# trigger_pickoff.net
KiCad netlist of a schematic drawn in EAGLE
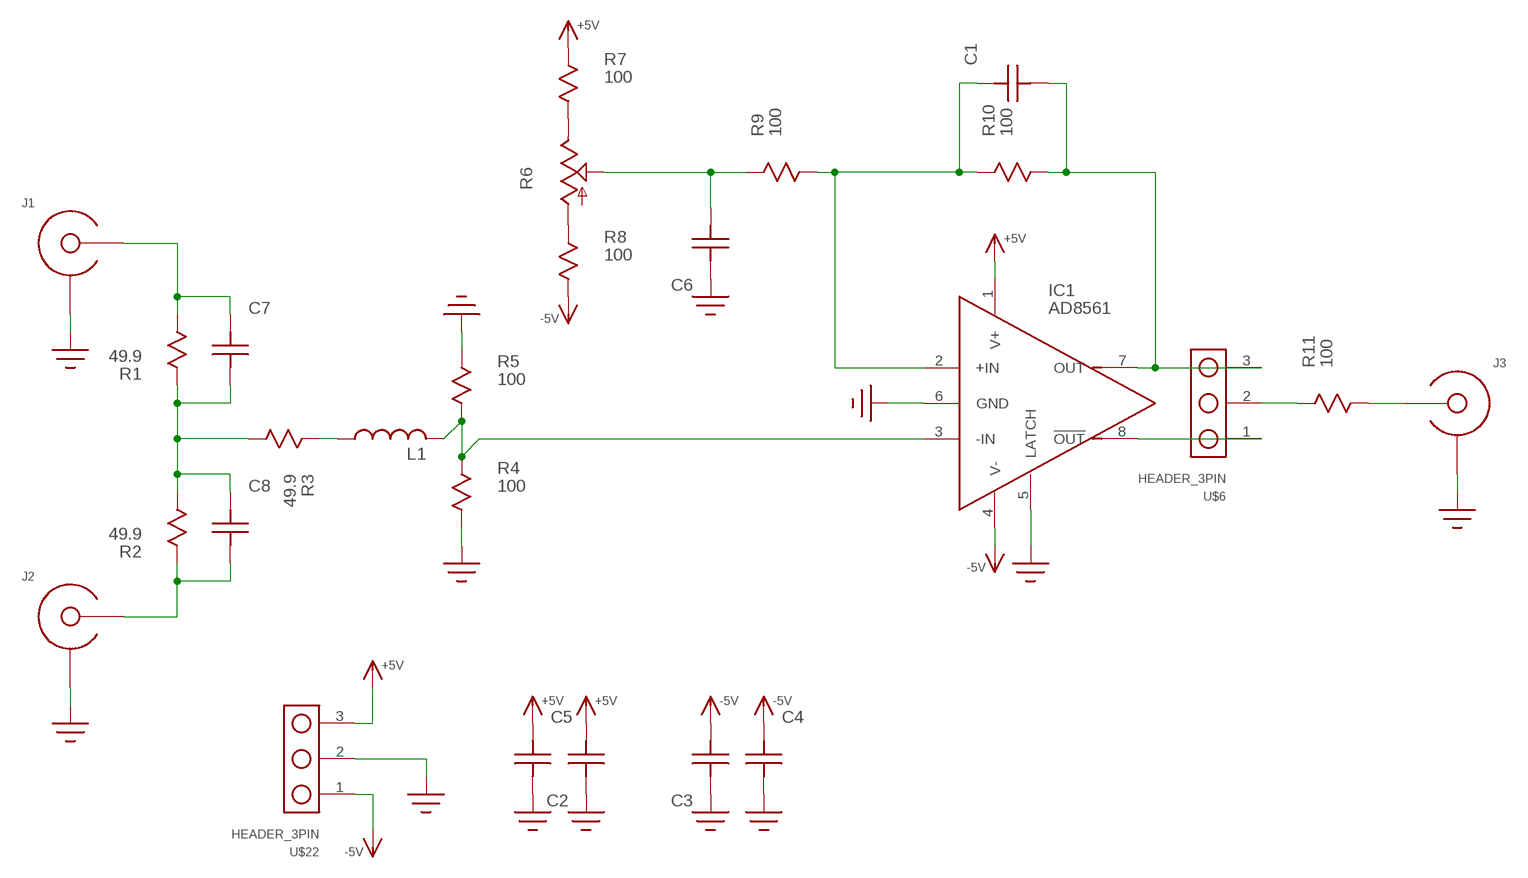
[diagram p0: schematic, sheet 1]

(export (version "E")
  (design (tool "Eeschema 10.0.6"))
  (components
    (comp (ref "C1")
      (value "C0603")
      (footprint "eagle-import:C0603")
      (libsource (lib "eagle-import") (part "C0603"))
    )
    (comp (ref "C2")
      (value "C0603")
      (footprint "eagle-import:C0603")
      (libsource (lib "eagle-import") (part "C0603"))
    )
    (comp (ref "C3")
      (value "C0603")
      (footprint "eagle-import:C0603")
      (libsource (lib "eagle-import") (part "C0603"))
    )
    (comp (ref "C4")
      (value "C0805")
      (footprint "eagle-import:0805")
      (libsource (lib "eagle-import") (part "C0805"))
    )
    (comp (ref "C5")
      (value "C0805")
      (footprint "eagle-import:0805")
      (libsource (lib "eagle-import") (part "C0805"))
    )
    (comp (ref "C6")
      (value "C0603")
      (footprint "eagle-import:C0603")
      (libsource (lib "eagle-import") (part "C0603"))
    )
    (comp (ref "C7")
      (value "C0603")
      (footprint "eagle-import:C0603")
      (libsource (lib "eagle-import") (part "C0603"))
    )
    (comp (ref "C8")
      (value "C0603")
      (footprint "eagle-import:C0603")
      (libsource (lib "eagle-import") (part "C0603"))
    )
    (comp (ref "IC1")
      (value "AD8561")
      (footprint "eagle-import:SOIC8")
      (libsource (lib "eagle-import") (part "AD8561"))
    )
    (comp (ref "J1")
      (value "EDGE_LAUNCH_JACK")
      (footprint "eagle-import:EDGE_LAUNCH_RF_CON")
      (libsource (lib "eagle-import") (part "EDGE_LAUNCH_JACK"))
    )
    (comp (ref "J2")
      (value "EDGE_LAUNCH_JACK")
      (footprint "eagle-import:EDGE_LAUNCH_RF_CON")
      (libsource (lib "eagle-import") (part "EDGE_LAUNCH_JACK"))
    )
    (comp (ref "J3")
      (value "EDGE_LAUNCH_JACK")
      (footprint "eagle-import:EDGE_LAUNCH_RF_CON")
      (libsource (lib "eagle-import") (part "EDGE_LAUNCH_JACK"))
    )
    (comp (ref "L1")
      (value "INDUCTOR")
      (footprint "eagle-import:R0603")
      (libsource (lib "eagle-import") (part "INDUCTOR"))
    )
    (comp (ref "R1")
      (value "49.9")
      (footprint "eagle-import:R0603")
      (libsource (lib "eagle-import") (part "R0603"))
    )
    (comp (ref "R2")
      (value "49.9")
      (footprint "eagle-import:R0603")
      (libsource (lib "eagle-import") (part "R0603"))
    )
    (comp (ref "R3")
      (value "49.9")
      (footprint "eagle-import:R0603")
      (libsource (lib "eagle-import") (part "R0603"))
    )
    (comp (ref "R4")
      (value "100")
      (footprint "eagle-import:R0603")
      (libsource (lib "eagle-import") (part "R0603"))
    )
    (comp (ref "R5")
      (value "100")
      (footprint "eagle-import:R0603")
      (libsource (lib "eagle-import") (part "R0603"))
    )
    (comp (ref "R6")
      (value "TRIM_US-SP19L")
      (footprint "eagle-import:SP19L")
      (libsource (lib "eagle-import") (part "TRIM_US-SP19L"))
    )
    (comp (ref "R7")
      (value "100")
      (footprint "eagle-import:R0603")
      (libsource (lib "eagle-import") (part "R0603"))
    )
    (comp (ref "R8")
      (value "100")
      (footprint "eagle-import:R0603")
      (libsource (lib "eagle-import") (part "R0603"))
    )
    (comp (ref "R9")
      (value "100")
      (footprint "eagle-import:R0603")
      (libsource (lib "eagle-import") (part "R0603"))
    )
    (comp (ref "R10")
      (value "100")
      (footprint "eagle-import:R0603")
      (libsource (lib "eagle-import") (part "R0603"))
    )
    (comp (ref "R11")
      (value "100")
      (footprint "eagle-import:R0603")
      (libsource (lib "eagle-import") (part "R0603"))
    )
    (comp (ref "U$6")
      (value "HEADER_3PIN")
      (footprint "eagle-import:HEADER_3PIN")
      (libsource (lib "eagle-import") (part "HEADER_3PIN"))
    )
    (comp (ref "U$22")
      (value "HEADER_3PIN")
      (footprint "eagle-import:HEADER_3PIN")
      (libsource (lib "eagle-import") (part "HEADER_3PIN"))
    )
  )
  (nets
    (net (code "1") (name "+5V") (class "Default")
      (node (ref "C2") (pin "P$1") (pinfunction "P$1_P$1") (pintype "bidirectional"))
      (node (ref "C5") (pin "P$2") (pinfunction "P$2_P$2") (pintype "bidirectional"))
      (node (ref "IC1") (pin "1") (pinfunction "V+_1") (pintype "bidirectional"))
      (node (ref "R7") (pin "P$1") (pinfunction "P$3_P$1") (pintype "bidirectional"))
      (node (ref "U$22") (pin "3") (pinfunction "3_3") (pintype "bidirectional"))
    )
    (net (code "2") (name "-5V") (class "Default")
      (node (ref "C3") (pin "P$1") (pinfunction "P$1_P$1") (pintype "bidirectional"))
      (node (ref "C4") (pin "P$2") (pinfunction "P$2_P$2") (pintype "bidirectional"))
      (node (ref "IC1") (pin "4") (pinfunction "V-_4") (pintype "bidirectional"))
      (node (ref "R8") (pin "P$2") (pinfunction "P$4_P$2") (pintype "bidirectional"))
      (node (ref "U$22") (pin "1") (pinfunction "1_1") (pintype "bidirectional"))
    )
    (net (code "3") (name "GND") (class "Default")
      (node (ref "C2") (pin "P$2") (pinfunction "P$2_P$2") (pintype "bidirectional"))
      (node (ref "C3") (pin "P$2") (pinfunction "P$2_P$2") (pintype "bidirectional"))
      (node (ref "C4") (pin "P$1") (pinfunction "P$1_P$1") (pintype "bidirectional"))
      (node (ref "C5") (pin "P$1") (pinfunction "P$1_P$1") (pintype "bidirectional"))
      (node (ref "C6") (pin "P$2") (pinfunction "P$2_P$2") (pintype "bidirectional"))
      (node (ref "IC1") (pin "5") (pinfunction "LATCH_5") (pintype "bidirectional"))
      (node (ref "IC1") (pin "6") (pinfunction "GND_6") (pintype "bidirectional"))
      (node (ref "J1") (pin "GND@1") (pinfunction "SHIELD_GND@1") (pintype "bidirectional"))
      (node (ref "J1") (pin "GND@10") (pinfunction "SHIELD_GND@10") (pintype "bidirectional"))
      (node (ref "J1") (pin "GND@11") (pinfunction "SHIELD_GND@11") (pintype "bidirectional"))
      (node (ref "J1") (pin "GND@12") (pinfunction "SHIELD_GND@12") (pintype "bidirectional"))
      (node (ref "J1") (pin "GND@2") (pinfunction "SHIELD_GND@2") (pintype "bidirectional"))
      (node (ref "J1") (pin "GND@3") (pinfunction "SHIELD_GND@3") (pintype "bidirectional"))
      (node (ref "J1") (pin "GND@4") (pinfunction "SHIELD_GND@4") (pintype "bidirectional"))
      (node (ref "J1") (pin "GND@5") (pinfunction "SHIELD_GND@5") (pintype "bidirectional"))
      (node (ref "J1") (pin "GND@6") (pinfunction "SHIELD_GND@6") (pintype "bidirectional"))
      (node (ref "J1") (pin "GND@7") (pinfunction "SHIELD_GND@7") (pintype "bidirectional"))
      (node (ref "J1") (pin "GND@8") (pinfunction "SHIELD_GND@8") (pintype "bidirectional"))
      (node (ref "J1") (pin "GND@9") (pinfunction "SHIELD_GND@9") (pintype "bidirectional"))
      (node (ref "J1") (pin "SHIELD@1") (pinfunction "SHIELD_SHIELD@1") (pintype "bidirectional"))
      (node (ref "J1") (pin "SHIELD@2") (pinfunction "SHIELD_SHIELD@2") (pintype "bidirectional"))
      (node (ref "J2") (pin "GND@1") (pinfunction "SHIELD_GND@1") (pintype "bidirectional"))
      (node (ref "J2") (pin "GND@10") (pinfunction "SHIELD_GND@10") (pintype "bidirectional"))
      (node (ref "J2") (pin "GND@11") (pinfunction "SHIELD_GND@11") (pintype "bidirectional"))
      (node (ref "J2") (pin "GND@12") (pinfunction "SHIELD_GND@12") (pintype "bidirectional"))
      (node (ref "J2") (pin "GND@2") (pinfunction "SHIELD_GND@2") (pintype "bidirectional"))
      (node (ref "J2") (pin "GND@3") (pinfunction "SHIELD_GND@3") (pintype "bidirectional"))
      (node (ref "J2") (pin "GND@4") (pinfunction "SHIELD_GND@4") (pintype "bidirectional"))
      (node (ref "J2") (pin "GND@5") (pinfunction "SHIELD_GND@5") (pintype "bidirectional"))
      (node (ref "J2") (pin "GND@6") (pinfunction "SHIELD_GND@6") (pintype "bidirectional"))
      (node (ref "J2") (pin "GND@7") (pinfunction "SHIELD_GND@7") (pintype "bidirectional"))
      (node (ref "J2") (pin "GND@8") (pinfunction "SHIELD_GND@8") (pintype "bidirectional"))
      (node (ref "J2") (pin "GND@9") (pinfunction "SHIELD_GND@9") (pintype "bidirectional"))
      (node (ref "J2") (pin "SHIELD@1") (pinfunction "SHIELD_SHIELD@1") (pintype "bidirectional"))
      (node (ref "J2") (pin "SHIELD@2") (pinfunction "SHIELD_SHIELD@2") (pintype "bidirectional"))
      (node (ref "J3") (pin "GND@1") (pinfunction "SHIELD_GND@1") (pintype "bidirectional"))
      (node (ref "J3") (pin "GND@10") (pinfunction "SHIELD_GND@10") (pintype "bidirectional"))
      (node (ref "J3") (pin "GND@11") (pinfunction "SHIELD_GND@11") (pintype "bidirectional"))
      (node (ref "J3") (pin "GND@12") (pinfunction "SHIELD_GND@12") (pintype "bidirectional"))
      (node (ref "J3") (pin "GND@2") (pinfunction "SHIELD_GND@2") (pintype "bidirectional"))
      (node (ref "J3") (pin "GND@3") (pinfunction "SHIELD_GND@3") (pintype "bidirectional"))
      (node (ref "J3") (pin "GND@4") (pinfunction "SHIELD_GND@4") (pintype "bidirectional"))
      (node (ref "J3") (pin "GND@5") (pinfunction "SHIELD_GND@5") (pintype "bidirectional"))
      (node (ref "J3") (pin "GND@6") (pinfunction "SHIELD_GND@6") (pintype "bidirectional"))
      (node (ref "J3") (pin "GND@7") (pinfunction "SHIELD_GND@7") (pintype "bidirectional"))
      (node (ref "J3") (pin "GND@8") (pinfunction "SHIELD_GND@8") (pintype "bidirectional"))
      (node (ref "J3") (pin "GND@9") (pinfunction "SHIELD_GND@9") (pintype "bidirectional"))
      (node (ref "J3") (pin "SHIELD@1") (pinfunction "SHIELD_SHIELD@1") (pintype "bidirectional"))
      (node (ref "J3") (pin "SHIELD@2") (pinfunction "SHIELD_SHIELD@2") (pintype "bidirectional"))
      (node (ref "R4") (pin "P$2") (pinfunction "P$4_P$2") (pintype "bidirectional"))
      (node (ref "R5") (pin "P$1") (pinfunction "P$3_P$1") (pintype "bidirectional"))
      (node (ref "U$22") (pin "2") (pinfunction "2_2") (pintype "bidirectional"))
    )
    (net (code "4") (name "Net-(IC1-+IN)") (class "Default")
      (node (ref "C1") (pin "P$2") (pinfunction "P$2_P$2") (pintype "bidirectional"))
      (node (ref "IC1") (pin "2") (pinfunction "+IN_2") (pintype "bidirectional"))
      (node (ref "R10") (pin "P$1") (pinfunction "P$3_P$1") (pintype "bidirectional"))
      (node (ref "R9") (pin "P$2") (pinfunction "P$4_P$2") (pintype "bidirectional"))
    )
    (net (code "5") (name "Net-(IC1--IN)") (class "Default")
      (node (ref "IC1") (pin "3") (pinfunction "-IN_3") (pintype "bidirectional"))
      (node (ref "L1") (pin "P$2") (pinfunction "2_P$2") (pintype "passive"))
      (node (ref "R4") (pin "P$1") (pinfunction "P$3_P$1") (pintype "bidirectional"))
      (node (ref "R5") (pin "P$2") (pinfunction "P$4_P$2") (pintype "bidirectional"))
    )
    (net (code "6") (name "Net-(IC1-OUT)") (class "Default")
      (node (ref "C1") (pin "P$1") (pinfunction "P$1_P$1") (pintype "bidirectional"))
      (node (ref "IC1") (pin "7") (pinfunction "OUT_7") (pintype "bidirectional"))
      (node (ref "R10") (pin "P$2") (pinfunction "P$4_P$2") (pintype "bidirectional"))
      (node (ref "U$6") (pin "3") (pinfunction "3_3") (pintype "bidirectional"))
    )
    (net (code "7") (name "Net-(IC1-~{OUT})") (class "Default")
      (node (ref "IC1") (pin "8") (pinfunction "~{OUT}_8") (pintype "bidirectional"))
      (node (ref "U$6") (pin "1") (pinfunction "1_1") (pintype "bidirectional"))
    )
    (net (code "8") (name "Net-(L1-1)") (class "Default")
      (node (ref "L1") (pin "P$1") (pinfunction "1_P$1") (pintype "passive"))
      (node (ref "R3") (pin "P$1") (pinfunction "P$3_P$1") (pintype "bidirectional"))
    )
    (net (code "9") (name "Net-(R1-P$3)") (class "Default")
      (node (ref "C7") (pin "P$1") (pinfunction "P$1_P$1") (pintype "bidirectional"))
      (node (ref "C8") (pin "P$2") (pinfunction "P$2_P$2") (pintype "bidirectional"))
      (node (ref "R1") (pin "P$1") (pinfunction "P$3_P$1") (pintype "bidirectional"))
      (node (ref "R2") (pin "P$2") (pinfunction "P$4_P$2") (pintype "bidirectional"))
      (node (ref "R3") (pin "P$2") (pinfunction "P$4_P$2") (pintype "bidirectional"))
    )
    (net (code "10") (name "Net-(R1-P$4)") (class "Default")
      (node (ref "C7") (pin "P$2") (pinfunction "P$2_P$2") (pintype "bidirectional"))
      (node (ref "J1") (pin "CENTER") (pinfunction "CENTER_CENTER") (pintype "bidirectional"))
      (node (ref "R1") (pin "P$2") (pinfunction "P$4_P$2") (pintype "bidirectional"))
    )
    (net (code "11") (name "Net-(R2-P$3)") (class "Default")
      (node (ref "C8") (pin "P$1") (pinfunction "P$1_P$1") (pintype "bidirectional"))
      (node (ref "J2") (pin "CENTER") (pinfunction "CENTER_CENTER") (pintype "bidirectional"))
      (node (ref "R2") (pin "P$1") (pinfunction "P$3_P$1") (pintype "bidirectional"))
    )
    (net (code "12") (name "Net-(R7-P$4)") (class "Default")
      (node (ref "R6") (pin "E") (pinfunction "E_E") (pintype "passive"))
      (node (ref "R7") (pin "P$2") (pinfunction "P$4_P$2") (pintype "bidirectional"))
    )
    (net (code "13") (name "Net-(R8-P$3)") (class "Default")
      (node (ref "R6") (pin "A") (pinfunction "A_A") (pintype "passive"))
      (node (ref "R8") (pin "P$1") (pinfunction "P$3_P$1") (pintype "bidirectional"))
    )
    (net (code "14") (name "Net-(R9-P$3)") (class "Default")
      (node (ref "C6") (pin "P$1") (pinfunction "P$1_P$1") (pintype "bidirectional"))
      (node (ref "R6") (pin "S") (pinfunction "S_S") (pintype "passive"))
      (node (ref "R9") (pin "P$1") (pinfunction "P$3_P$1") (pintype "bidirectional"))
    )
    (net (code "15") (name "Net-(R11-P$3)") (class "Default")
      (node (ref "R11") (pin "P$1") (pinfunction "P$3_P$1") (pintype "bidirectional"))
      (node (ref "U$6") (pin "2") (pinfunction "2_2") (pintype "bidirectional"))
    )
    (net (code "16") (name "Net-(R11-P$4)") (class "Default")
      (node (ref "J3") (pin "CENTER") (pinfunction "CENTER_CENTER") (pintype "bidirectional"))
      (node (ref "R11") (pin "P$2") (pinfunction "P$4_P$2") (pintype "bidirectional"))
    )
  )
)
